# ProPrj_Xros_rev_5_2026-01-20.net
KiCad netlist of a schematic drawn in EasyEDA Pro
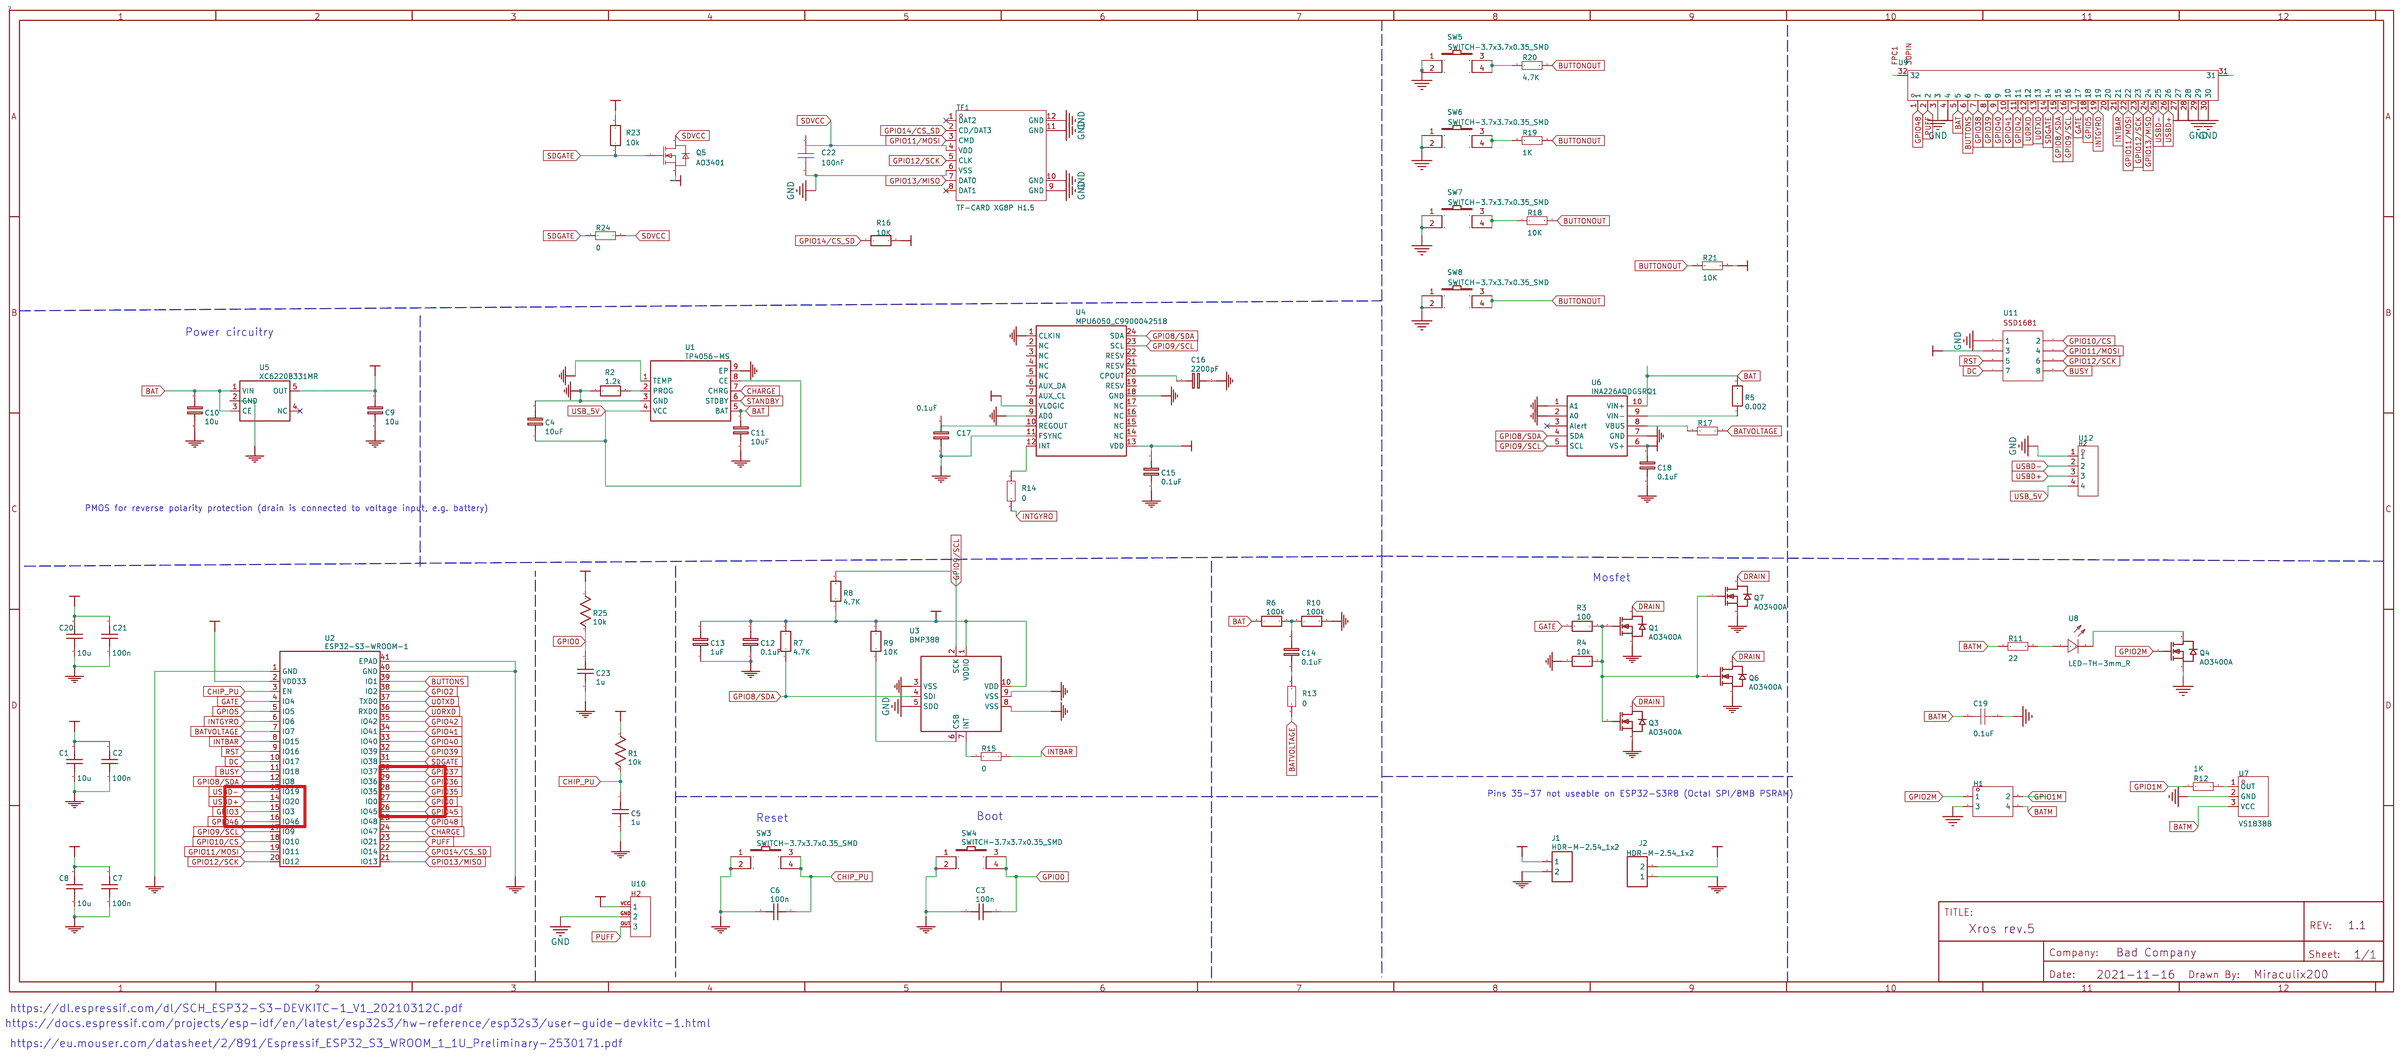
[diagram p0: schematic sheet]

(export (version "E")
  (design (tool "Eeschema 10.0.6"))
  (components
    (comp (ref "C1")
      (value "10u")
      (footprint "easyedapro:C0805")
      (fields (field (name "Contributor") "LCEDA_Lib"))
      (libsource (lib "easyedapro") (part "10u"))
    )
    (comp (ref "C2")
      (value "100n")
      (footprint "easyedapro:C0603")
      (fields (field (name "Contributor") "LCEDA_Lib"))
      (libsource (lib "easyedapro") (part "100n"))
    )
    (comp (ref "C3")
      (value "100n")
      (footprint "easyedapro:C0603")
      (fields (field (name "Contributor") "LCEDA_Lib"))
      (libsource (lib "easyedapro") (part "100n"))
    )
    (comp (ref "C4")
      (value "10uF")
      (footprint "easyedapro:C0603")
      (fields (field (name "Contributor") "LCEDA_Lib"))
      (libsource (lib "") (part "10uF_1"))
    )
    (comp (ref "C5")
      (value "1u")
      (footprint "easyedapro:C0603")
      (fields (field (name "Contributor") "LCEDA_Lib"))
      (libsource (lib "easyedapro") (part "1u"))
    )
    (comp (ref "C6")
      (value "100n")
      (footprint "easyedapro:C0603")
      (fields (field (name "Contributor") "LCEDA_Lib"))
      (libsource (lib "easyedapro") (part "100n"))
    )
    (comp (ref "C7")
      (value "100n")
      (footprint "easyedapro:C0603")
      (fields (field (name "Contributor") "LCEDA_Lib"))
      (libsource (lib "easyedapro") (part "100n"))
    )
    (comp (ref "C8")
      (value "10u")
      (footprint "easyedapro:C0805")
      (fields (field (name "Contributor") "LCEDA_Lib"))
      (libsource (lib "easyedapro") (part "10u"))
    )
    (comp (ref "C9")
      (value "10u")
      (footprint "easyedapro:C0805")
      (fields
        (field (name "Manufacturer Part") "CL10A105KB8NNNC")
        (field (name "Manufacturer") "SAMSUNG")
        (field (name "Contributor") "LCEDA_Lib")
      )
      (libsource (lib "") (part "10u_1"))
    )
    (comp (ref "C10")
      (value "10u")
      (footprint "easyedapro:C0805")
      (fields
        (field (name "Manufacturer Part") "CL10A105KB8NNNC")
        (field (name "Manufacturer") "SAMSUNG")
        (field (name "Contributor") "LCEDA_Lib")
      )
      (libsource (lib "") (part "10u_1"))
    )
    (comp (ref "C11")
      (value "10uF")
      (footprint "easyedapro:C0603")
      (fields (field (name "Contributor") "LCEDA_Lib"))
      (libsource (lib "easyedapro") (part "10uF"))
    )
    (comp (ref "C12")
      (value "0.1uF")
      (footprint "easyedapro:C0603")
      (fields (field (name "Contributor") "LCEDA_Lib"))
      (libsource (lib "") (part "0.1uF_2"))
    )
    (comp (ref "C13")
      (value "1uF")
      (footprint "easyedapro:C0603")
      (fields (field (name "Contributor") "LCEDA_Lib"))
      (libsource (lib "easyedapro") (part "1uF"))
    )
    (comp (ref "C14")
      (value "0.1uF")
      (footprint "easyedapro:C0603")
      (fields (field (name "Contributor") "LCEDA_Lib"))
      (libsource (lib "") (part "0.1uF_2"))
    )
    (comp (ref "C15")
      (value "0.1uF")
      (footprint "easyedapro:C0603")
      (fields (field (name "Contributor") "LCEDA_Lib"))
      (libsource (lib "") (part "0.1uF_2"))
    )
    (comp (ref "C16")
      (value "2200pF")
      (footprint "easyedapro:C0603")
      (fields (field (name "Contributor") "LCEDA_Lib"))
      (libsource (lib "easyedapro") (part "2200pF"))
    )
    (comp (ref "C17")
      (value "0.1uF")
      (footprint "easyedapro:C0603")
      (fields (field (name "Contributor") "LCEDA_Lib"))
      (libsource (lib "easyedapro") (part "0.1uF"))
    )
    (comp (ref "C18")
      (value "0.1uF")
      (footprint "easyedapro:C0603")
      (fields (field (name "Contributor") "LCEDA_Lib"))
      (libsource (lib "") (part "0.1uF_1"))
    )
    (comp (ref "C19")
      (value "0.1uF")
      (footprint "easyedapro:C0201")
      (libsource (lib "easyedapro") (part "CAP"))
    )
    (comp (ref "C20")
      (value "10u")
      (footprint "easyedapro:C0805")
      (fields (field (name "Contributor") "LCEDA_Lib"))
      (libsource (lib "easyedapro") (part "10u"))
    )
    (comp (ref "C21")
      (value "100n")
      (footprint "easyedapro:C0603")
      (fields (field (name "Contributor") "LCEDA_Lib"))
      (libsource (lib "easyedapro") (part "100n"))
    )
    (comp (ref "C22")
      (value "100nF")
      (footprint "easyedapro:C0201")
      (libsource (lib "easyedapro") (part "CAP"))
    )
    (comp (ref "C23")
      (value "1u")
      (footprint "easyedapro:C0603")
      (fields (field (name "Contributor") "LCEDA_Lib"))
      (libsource (lib "easyedapro") (part "1u"))
    )
    (comp (ref "H1")
      (value "~")
      (footprint "easyedapro:HDR-TH_4P-P2.54-V-F-R2-C2-S2.54")
      (libsource (lib "easyedapro") (part "HDR-F-2.54_2x2"))
    )
    (comp (ref "J1")
      (value "HDR-M-2.54_1x2")
      (footprint "easyedapro:HDR-M-2.54_1X2")
      (fields (field (name "Contributor") "LCEDA_Lib"))
      (libsource (lib "easyedapro") (part "HDR-M-2.54_1x2"))
    )
    (comp (ref "J2")
      (value "HDR-M-2.54_1x2")
      (footprint "easyedapro:HDR-M-2.54_1X2")
      (fields (field (name "Contributor") "LCEDA_Lib"))
      (libsource (lib "") (part "HDR-M-2.54_1x2_1"))
    )
    (comp (ref "Q1")
      (value "AO3400A")
      (footprint "easyedapro:SOT-23-3_L2.9-W1.3-P1.90-LS2.4-BR")
      (fields (field (name "Manufacturer") "AOS"))
      (libsource (lib "easyedapro") (part "AO3400A"))
    )
    (comp (ref "Q3")
      (value "AO3400A")
      (footprint "easyedapro:SOT-23-3_L2.9-W1.3-P1.90-LS2.4-BR")
      (fields (field (name "Manufacturer") "AOS"))
      (libsource (lib "easyedapro") (part "AO3400A"))
    )
    (comp (ref "Q4")
      (value "AO3400A")
      (footprint "easyedapro:SOT-23-3_L2.9-W1.3-P1.90-LS2.4-BR")
      (fields (field (name "Manufacturer") "AOS"))
      (libsource (lib "easyedapro") (part "AO3400A"))
    )
    (comp (ref "Q5")
      (value "AO3401")
      (footprint "easyedapro:SOT-23-3_L2.9-W1.4-P1.90-LS2.5-BR")
      (fields (field (name "Manufacturer") "GMIC(绿微)"))
      (libsource (lib "easyedapro") (part "AO3401_C53261043"))
    )
    (comp (ref "Q6")
      (value "AO3400A")
      (footprint "easyedapro:SOT-23-3_L2.9-W1.3-P1.90-LS2.4-BR")
      (fields (field (name "Manufacturer") "AOS"))
      (libsource (lib "easyedapro") (part "AO3400A"))
    )
    (comp (ref "Q7")
      (value "AO3400A")
      (footprint "easyedapro:SOT-23-3_L2.9-W1.3-P1.90-LS2.4-BR")
      (fields (field (name "Manufacturer") "AOS"))
      (libsource (lib "easyedapro") (part "AO3400A"))
    )
    (comp (ref "R1")
      (value "10k")
      (footprint "easyedapro:R0603")
      (fields (field (name "Contributor") "LCEDA_Lib"))
      (libsource (lib "") (part "10k_2"))
    )
    (comp (ref "R2")
      (value "1.2k")
      (footprint "easyedapro:R0603")
      (fields (field (name "Contributor") "LCEDA_Lib"))
      (libsource (lib "easyedapro") (part "1.2k"))
    )
    (comp (ref "R3")
      (value "100")
      (footprint "easyedapro:R0603")
      (fields (field (name "Contributor") "LCEDA_Lib"))
      (libsource (lib "easyedapro") (part "100"))
    )
    (comp (ref "R4")
      (value "10k")
      (footprint "easyedapro:R0603")
      (fields (field (name "Contributor") "LCEDA_Lib"))
      (libsource (lib "easyedapro") (part "10k"))
    )
    (comp (ref "R5")
      (value "0.002")
      (footprint "easyedapro:R0603")
      (fields (field (name "Contributor") "LCEDA_Lib"))
      (libsource (lib "easyedapro") (part "0.002"))
    )
    (comp (ref "R6")
      (value "100k")
      (footprint "easyedapro:R0603")
      (fields (field (name "Contributor") "LCEDA_Lib"))
      (libsource (lib "easyedapro") (part "100k"))
    )
    (comp (ref "R7")
      (value "4.7K")
      (footprint "easyedapro:R0603")
      (fields (field (name "Contributor") "LCEDA_Lib"))
      (libsource (lib "") (part "10k_1"))
    )
    (comp (ref "R8")
      (value "4.7K")
      (footprint "easyedapro:R0603")
      (fields (field (name "Contributor") "LCEDA_Lib"))
      (libsource (lib "easyedapro") (part "10K"))
    )
    (comp (ref "R9")
      (value "10K")
      (footprint "easyedapro:R0603")
      (fields (field (name "Contributor") "LCEDA_Lib"))
      (libsource (lib "easyedapro") (part "10K"))
    )
    (comp (ref "R10")
      (value "100k")
      (footprint "easyedapro:R0603")
      (fields (field (name "Contributor") "LCEDA_Lib"))
      (libsource (lib "easyedapro") (part "100k"))
    )
    (comp (ref "R11") (value "22") (footprint "easyedapro:R0805") (libsource (lib "easyedapro") (part "Res")))
    (comp (ref "R12") (value "1K") (footprint "easyedapro:R0805") (libsource (lib "easyedapro") (part "Res")))
    (comp (ref "R13") (value "0") (footprint "easyedapro:R0805") (libsource (lib "easyedapro") (part "Res")))
    (comp (ref "R14") (value "0") (footprint "easyedapro:R0805") (libsource (lib "easyedapro") (part "Res")))
    (comp (ref "R15") (value "0") (footprint "easyedapro:R0805") (libsource (lib "easyedapro") (part "Res")))
    (comp (ref "R16")
      (value "10K")
      (footprint "easyedapro:R0603")
      (fields (field (name "Contributor") "LCEDA_Lib"))
      (libsource (lib "easyedapro") (part "1.2k"))
    )
    (comp (ref "R17") (value "0") (footprint "easyedapro:R0805") (libsource (lib "easyedapro") (part "Res")))
    (comp (ref "R18")
      (value "10K")
      (footprint "easyedapro:R0805")
      (libsource (lib "easyedapro") (part "Res"))
    )
    (comp (ref "R19") (value "1K") (footprint "easyedapro:R0805") (libsource (lib "easyedapro") (part "Res")))
    (comp (ref "R20")
      (value "4.7K")
      (footprint "easyedapro:R0805")
      (libsource (lib "easyedapro") (part "Res"))
    )
    (comp (ref "R21")
      (value "10K")
      (footprint "easyedapro:R0805")
      (libsource (lib "easyedapro") (part "Res"))
    )
    (comp (ref "R23")
      (value "10k")
      (footprint "easyedapro:R0603")
      (fields (field (name "Contributor") "LCEDA_Lib"))
      (libsource (lib "easyedapro") (part "10k"))
    )
    (comp (ref "R24") (value "0") (footprint "easyedapro:R0805") (libsource (lib "easyedapro") (part "Res")))
    (comp (ref "R25")
      (value "10k")
      (footprint "easyedapro:R0603")
      (fields (field (name "Contributor") "LCEDA_Lib"))
      (libsource (lib "") (part "10k_2"))
    )
    (comp (ref "SW3")
      (value "SWITCH-3.7x3.7x0.35_SMD")
      (footprint "easyedapro:SWITCH-3.7X3.7X0.8_SMD")
      (fields (field (name "Manufacturer") "BBJ") (field (name "Contributor") "Conrad Lagorio"))
      (libsource (lib "easyedapro") (part "SWITCH-3.7x3.7x0.35_SMD"))
    )
    (comp (ref "SW4")
      (value "SWITCH-3.7x3.7x0.35_SMD")
      (footprint "easyedapro:SWITCH-3.7X3.7X0.8_SMD")
      (fields (field (name "Manufacturer") "BBJ") (field (name "Contributor") "Conrad Lagorio"))
      (libsource (lib "easyedapro") (part "SWITCH-3.7x3.7x0.35_SMD"))
    )
    (comp (ref "SW5")
      (value "SWITCH-3.7x3.7x0.35_SMD")
      (footprint "easyedapro:SWITCH-3.7X3.7X0.8_SMD")
      (fields (field (name "Manufacturer") "BBJ") (field (name "Contributor") "Conrad Lagorio"))
      (libsource (lib "easyedapro") (part "SWITCH-3.7x3.7x0.35_SMD"))
    )
    (comp (ref "SW6")
      (value "SWITCH-3.7x3.7x0.35_SMD")
      (footprint "easyedapro:SWITCH-3.7X3.7X0.8_SMD")
      (fields (field (name "Manufacturer") "BBJ") (field (name "Contributor") "Conrad Lagorio"))
      (libsource (lib "easyedapro") (part "SWITCH-3.7x3.7x0.35_SMD"))
    )
    (comp (ref "SW7")
      (value "SWITCH-3.7x3.7x0.35_SMD")
      (footprint "easyedapro:SWITCH-3.7X3.7X0.8_SMD")
      (fields (field (name "Manufacturer") "BBJ") (field (name "Contributor") "Conrad Lagorio"))
      (libsource (lib "easyedapro") (part "SWITCH-3.7x3.7x0.35_SMD"))
    )
    (comp (ref "SW8")
      (value "SWITCH-3.7x3.7x0.35_SMD")
      (footprint "easyedapro:SWITCH-3.7X3.7X0.8_SMD")
      (fields (field (name "Manufacturer") "BBJ") (field (name "Contributor") "Conrad Lagorio"))
      (libsource (lib "easyedapro") (part "SWITCH-3.7x3.7x0.35_SMD"))
    )
    (comp (ref "TF1")
      (value "TF-CARD XG8P H1.5")
      (footprint "easyedapro:TF-SMD_TF-CARD-XG8P-H1.5")
      (fields (field (name "Manufacturer") "SHOU HAN(首韩)"))
      (libsource (lib "easyedapro") (part "TF-CARD XG8P H1.5"))
    )
    (comp (ref "U1")
      (value "TP4056-MS")
      (footprint "easyedapro:SOP-8_L4.9-W3.9-P1.27-LS6.0-TL-EP")
      (fields (field (name "Manufacturer") "MSKSEMI(美森科)") (field (name "Contributor") "lcsc"))
      (libsource (lib "easyedapro") (part "TP4056-MS"))
    )
    (comp (ref "U2")
      (value "ESP32-S3-WROOM-1")
      (footprint "easyedapro:ESP32-S3-WROOM-1")
      (fields (field (name "Manufacturer") "Espressif Systems") (field (name "Contributor") "max30012540"))
      (libsource (lib "easyedapro") (part "ESP32-S3-WROOM-1"))
    )
    (comp (ref "U3")
      (value "BMP388")
      (footprint "easyedapro:SENSORM-SMD_BMP388")
      (fields (field (name "Manufacturer") "Bosch(博世)") (field (name "Contributor") "LCSC"))
      (libsource (lib "easyedapro") (part "BMP388"))
    )
    (comp (ref "U4")
      (value "MPU6050_C9900042518")
      (footprint "easyedapro:QFN-24_L4.0-W4.0-P0.50-BL")
      (fields (field (name "Manufacturer Part") "MPU6050") (field (name "Contributor") "lcsc"))
      (libsource (lib "easyedapro") (part "MPU6050_C9900042518"))
    )
    (comp (ref "U5")
      (value "XC6220B331MR")
      (footprint "easyedapro:SOT-23-5_L2.9-W1.6-P0.95-LS2.8-BR")
      (fields (field (name "Manufacturer") "TECH PUBLIC(台舟)") (field (name "Contributor") "lcsc"))
      (libsource (lib "easyedapro") (part "XC6220B331MR"))
    )
    (comp (ref "U6")
      (value "INA226AQDGSRQ1")
      (footprint "easyedapro:VSSOP-10_L3.0-W3.0-P0.50-LS4.9-BL")
      (fields (field (name "Manufacturer") "TI(德州仪器)") (field (name "Contributor") "lcsc"))
      (libsource (lib "easyedapro") (part "INA226AQDGSRQ1"))
    )
    (comp (ref "U7")
      (value "VS1838B")
      (footprint "easyedapro:OPTO-TH_VS1838B")
      (libsource (lib "easyedapro") (part "VS1838B"))
    )
    (comp (ref "U8")
      (value "LED-TH-3mm_R")
      (footprint "easyedapro:LED-TH_BD5.4-P2.54-FD_RED")
      (libsource (lib "easyedapro") (part "LED-TH-3MM_R"))
    )
    (comp (ref "U9")
      (value "~")
      (footprint "easyedapro:26PIN-FDD")
      (libsource (lib "easyedapro") (part "26PIN-dff"))
    )
    (comp (ref "U10")
      (value "~")
      (footprint "easyedapro:Puff sensor")
      (libsource (lib "easyedapro") (part "Puff sensor"))
    )
    (comp (ref "U11")
      (value "~")
      (footprint "easyedapro:HDR-TH_8P-P0.6")
      (libsource (lib "easyedapro") (part "HDR-TH_8P-P0.6"))
    )
    (comp (ref "U12")
      (value "~")
      (footprint "easyedapro:USB-CONNECTOR-4-PIN")
      (libsource (lib "easyedapro") (part "USB-CONNECTOR-OUT"))
    )
  )
  (nets
    (net (code "1") (name "3V3") (class "Default")
      (node (ref "C1") (pin "2") (pinfunction "2_2") (pintype "unspecified"))
      (node (ref "C12") (pin "2") (pinfunction "2_2") (pintype "unspecified"))
      (node (ref "C13") (pin "2") (pinfunction "2_2") (pintype "unspecified"))
      (node (ref "C15") (pin "2") (pinfunction "2_2") (pintype "unspecified"))
      (node (ref "C18") (pin "1") (pinfunction "1_1") (pintype "unspecified"))
      (node (ref "C2") (pin "2") (pinfunction "2_2") (pintype "unspecified"))
      (node (ref "C20") (pin "2") (pinfunction "2_2") (pintype "unspecified"))
      (node (ref "C21") (pin "2") (pinfunction "2_2") (pintype "unspecified"))
      (node (ref "C7") (pin "2") (pinfunction "2_2") (pintype "unspecified"))
      (node (ref "C8") (pin "2") (pinfunction "2_2") (pintype "unspecified"))
      (node (ref "C9") (pin "1") (pinfunction "1_1") (pintype "unspecified"))
      (node (ref "J1") (pin "1") (pinfunction "1_1") (pintype "unspecified"))
      (node (ref "Q5") (pin "2") (pinfunction "S_2") (pintype "unspecified"))
      (node (ref "R1") (pin "1") (pinfunction "1_1") (pintype "unspecified"))
      (node (ref "R16") (pin "2") (pinfunction "2_2") (pintype "unspecified"))
      (node (ref "R23") (pin "2") (pinfunction "2_2") (pintype "unspecified"))
      (node (ref "R25") (pin "1") (pinfunction "1_1") (pintype "unspecified"))
      (node (ref "R7") (pin "2") (pinfunction "2_2") (pintype "unspecified"))
      (node (ref "R8") (pin "1") (pinfunction "1_1") (pintype "unspecified"))
      (node (ref "R9") (pin "2") (pinfunction "2_2") (pintype "unspecified"))
      (node (ref "U10") (pin "VCC") (pinfunction "1_VCC") (pintype "unspecified"))
      (node (ref "U11") (pin "3") (pinfunction "3_3") (pintype "input"))
      (node (ref "U2") (pin "2") (pinfunction "VDD33_2") (pintype "unspecified"))
      (node (ref "U3") (pin "1") (pinfunction "VDDIO_1") (pintype "unspecified"))
      (node (ref "U3") (pin "10") (pinfunction "VDD_10") (pintype "unspecified"))
      (node (ref "U4") (pin "13") (pinfunction "VDD_13") (pintype "unspecified"))
      (node (ref "U4") (pin "8") (pinfunction "VLOGIC_8") (pintype "unspecified"))
      (node (ref "U5") (pin "5") (pinfunction "OUT_5") (pintype "unspecified"))
      (node (ref "U6") (pin "6") (pinfunction "VS+_6") (pintype "unspecified"))
      (node (ref "U9") (pin "27") (pinfunction "27_27") (pintype "input"))
      (node (ref "U9") (pin "28") (pinfunction "28_28") (pintype "input"))
      (node (ref "U9") (pin "4") (pinfunction "4_4") (pintype "input"))
    )
    (net (code "2") (name "3V3_BUT") (class "Default")
      (node (ref "R21") (pin "2") (pinfunction "2_2") (pintype "input"))
    )
    (net (code "3") (name "BAT") (class "Default")
      (node (ref "C10") (pin "1") (pinfunction "1_1") (pintype "unspecified"))
      (node (ref "C11") (pin "1") (pinfunction "1_1") (pintype "unspecified"))
      (node (ref "R5") (pin "2") (pinfunction "2_2") (pintype "unspecified"))
      (node (ref "R6") (pin "1") (pinfunction "1_1") (pintype "unspecified"))
      (node (ref "U1") (pin "5") (pinfunction "BAT_5") (pintype "unspecified"))
      (node (ref "U5") (pin "1") (pinfunction "VIN_1") (pintype "unspecified"))
      (node (ref "U5") (pin "3") (pinfunction "CE_3") (pintype "unspecified"))
      (node (ref "U6") (pin "10") (pinfunction "VIN+_10") (pintype "unspecified"))
      (node (ref "U9") (pin "5") (pinfunction "5_5") (pintype "input"))
    )
    (net (code "4") (name "BATM") (class "Default")
      (node (ref "C19") (pin "2") (pinfunction "2_2") (pintype "input"))
      (node (ref "H1") (pin "4") (pinfunction "4_4") (pintype "input"))
      (node (ref "R11") (pin "1") (pinfunction "1_1") (pintype "input"))
      (node (ref "U7") (pin "3") (pinfunction "VCC_3") (pintype "unspecified"))
    )
    (net (code "5") (name "BATVOLTAGE") (class "Default")
      (node (ref "R13") (pin "1") (pinfunction "1_1") (pintype "input"))
      (node (ref "R17") (pin "2") (pinfunction "2_2") (pintype "input"))
      (node (ref "U2") (pin "7") (pinfunction "IO7_7") (pintype "unspecified"))
    )
    (net (code "6") (name "BUSY") (class "Default")
      (node (ref "U11") (pin "8") (pinfunction "8_8") (pintype "input"))
      (node (ref "U2") (pin "11") (pinfunction "IO18_11") (pintype "unspecified"))
    )
    (net (code "7") (name "BUTTONOUT") (class "Default")
      (node (ref "R18") (pin "2") (pinfunction "2_2") (pintype "input"))
      (node (ref "R19") (pin "2") (pinfunction "2_2") (pintype "input"))
      (node (ref "R20") (pin "2") (pinfunction "2_2") (pintype "input"))
      (node (ref "R21") (pin "1") (pinfunction "1_1") (pintype "input"))
      (node (ref "SW8") (pin "3") (pinfunction "3_3") (pintype "input"))
      (node (ref "SW8") (pin "4") (pinfunction "4_4") (pintype "input"))
    )
    (net (code "8") (name "BUTTONS") (class "Default")
      (node (ref "U2") (pin "39") (pinfunction "IO1_39") (pintype "unspecified"))
      (node (ref "U9") (pin "6") (pinfunction "6_6") (pintype "input"))
    )
    (net (code "9") (name "CHARGE") (class "Default")
      (node (ref "U1") (pin "7") (pinfunction "CHRG_7") (pintype "unspecified"))
      (node (ref "U2") (pin "24") (pinfunction "IO47_24") (pintype "unspecified"))
    )
    (net (code "10") (name "CHIP_PU") (class "Default")
      (node (ref "C5") (pin "1") (pinfunction "1_1") (pintype "unspecified"))
      (node (ref "C6") (pin "1") (pinfunction "1_1") (pintype "unspecified"))
      (node (ref "R1") (pin "2") (pinfunction "2_2") (pintype "unspecified"))
      (node (ref "SW3") (pin "3") (pinfunction "3_3") (pintype "input"))
      (node (ref "SW3") (pin "4") (pinfunction "4_4") (pintype "input"))
      (node (ref "U2") (pin "3") (pinfunction "EN_3") (pintype "unspecified"))
    )
    (net (code "11") (name "DC") (class "Default")
      (node (ref "U11") (pin "7") (pinfunction "7_7") (pintype "input"))
      (node (ref "U2") (pin "10") (pinfunction "IO17_10") (pintype "unspecified"))
    )
    (net (code "12") (name "DRAIN") (class "Default")
      (node (ref "Q1") (pin "3") (pinfunction "D_3") (pintype "unspecified"))
      (node (ref "Q3") (pin "3") (pinfunction "D_3") (pintype "unspecified"))
      (node (ref "Q6") (pin "3") (pinfunction "D_3") (pintype "unspecified"))
      (node (ref "Q7") (pin "3") (pinfunction "D_3") (pintype "unspecified"))
    )
    (net (code "13") (name "GATE") (class "Default")
      (node (ref "R3") (pin "1") (pinfunction "1_1") (pintype "unspecified"))
      (node (ref "U2") (pin "4") (pinfunction "IO4_4") (pintype "unspecified"))
      (node (ref "U9") (pin "17") (pinfunction "17_17") (pintype "input"))
    )
    (net (code "14") (name "GND") (class "Default")
      (node (ref "C1") (pin "1") (pinfunction "1_1") (pintype "unspecified"))
      (node (ref "C10") (pin "2") (pinfunction "2_2") (pintype "unspecified"))
      (node (ref "C11") (pin "2") (pinfunction "2_2") (pintype "unspecified"))
      (node (ref "C12") (pin "1") (pinfunction "1_1") (pintype "unspecified"))
      (node (ref "C13") (pin "1") (pinfunction "1_1") (pintype "unspecified"))
      (node (ref "C15") (pin "1") (pinfunction "1_1") (pintype "unspecified"))
      (node (ref "C16") (pin "2") (pinfunction "2_2") (pintype "unspecified"))
      (node (ref "C17") (pin "2") (pinfunction "2_2") (pintype "unspecified"))
      (node (ref "C18") (pin "2") (pinfunction "2_2") (pintype "unspecified"))
      (node (ref "C2") (pin "1") (pinfunction "1_1") (pintype "unspecified"))
      (node (ref "C20") (pin "1") (pinfunction "1_1") (pintype "unspecified"))
      (node (ref "C21") (pin "1") (pinfunction "1_1") (pintype "unspecified"))
      (node (ref "C22") (pin "2") (pinfunction "2_2") (pintype "input"))
      (node (ref "C23") (pin "2") (pinfunction "2_2") (pintype "unspecified"))
      (node (ref "C3") (pin "2") (pinfunction "2_2") (pintype "unspecified"))
      (node (ref "C4") (pin "2") (pinfunction "2_2") (pintype "unspecified"))
      (node (ref "C5") (pin "2") (pinfunction "2_2") (pintype "unspecified"))
      (node (ref "C6") (pin "2") (pinfunction "2_2") (pintype "unspecified"))
      (node (ref "C7") (pin "1") (pinfunction "1_1") (pintype "unspecified"))
      (node (ref "C8") (pin "1") (pinfunction "1_1") (pintype "unspecified"))
      (node (ref "C9") (pin "2") (pinfunction "2_2") (pintype "unspecified"))
      (node (ref "J1") (pin "2") (pinfunction "2_2") (pintype "unspecified"))
      (node (ref "J2") (pin "1") (pinfunction "1_1") (pintype "unspecified"))
      (node (ref "Q1") (pin "2") (pinfunction "S_2") (pintype "unspecified"))
      (node (ref "Q3") (pin "2") (pinfunction "S_2") (pintype "unspecified"))
      (node (ref "Q6") (pin "2") (pinfunction "S_2") (pintype "unspecified"))
      (node (ref "Q7") (pin "2") (pinfunction "S_2") (pintype "unspecified"))
      (node (ref "R10") (pin "2") (pinfunction "2_2") (pintype "unspecified"))
      (node (ref "R2") (pin "1") (pinfunction "1_1") (pintype "unspecified"))
      (node (ref "R4") (pin "1") (pinfunction "1_1") (pintype "unspecified"))
      (node (ref "SW3") (pin "1") (pinfunction "1_1") (pintype "input"))
      (node (ref "SW3") (pin "2") (pinfunction "2_2") (pintype "input"))
      (node (ref "SW4") (pin "1") (pinfunction "1_1") (pintype "input"))
      (node (ref "SW4") (pin "2") (pinfunction "2_2") (pintype "input"))
      (node (ref "TF1") (pin "10") (pinfunction "GND_10") (pintype "unspecified"))
      (node (ref "TF1") (pin "11") (pinfunction "GND_11") (pintype "unspecified"))
      (node (ref "TF1") (pin "12") (pinfunction "GND_12") (pintype "unspecified"))
      (node (ref "TF1") (pin "6") (pinfunction "VSS_6") (pintype "unspecified"))
      (node (ref "TF1") (pin "9") (pinfunction "GND_9") (pintype "unspecified"))
      (node (ref "U1") (pin "1") (pinfunction "TEMP_1") (pintype "unspecified"))
      (node (ref "U1") (pin "3") (pinfunction "GND_3") (pintype "unspecified"))
      (node (ref "U1") (pin "9") (pinfunction "EP_9") (pintype "unspecified"))
      (node (ref "U10") (pin "GND") (pinfunction "2_GND") (pintype "unspecified"))
      (node (ref "U11") (pin "1") (pinfunction "1_1") (pintype "input"))
      (node (ref "U12") (pin "1") (pinfunction "1_1") (pintype "input"))
      (node (ref "U2") (pin "1") (pinfunction "GND_1") (pintype "unspecified"))
      (node (ref "U2") (pin "40") (pinfunction "GND_40") (pintype "unspecified"))
      (node (ref "U2") (pin "41") (pinfunction "EPAD_41") (pintype "unspecified"))
      (node (ref "U3") (pin "3") (pinfunction "VSS_3") (pintype "unspecified"))
      (node (ref "U3") (pin "5") (pinfunction "SDO_5") (pintype "unspecified"))
      (node (ref "U3") (pin "8") (pinfunction "VSS_8") (pintype "unspecified"))
      (node (ref "U3") (pin "9") (pinfunction "VSS_9") (pintype "unspecified"))
      (node (ref "U4") (pin "1") (pinfunction "CLKIN_1") (pintype "unspecified"))
      (node (ref "U4") (pin "11") (pinfunction "FSYNC_11") (pintype "unspecified"))
      (node (ref "U4") (pin "18") (pinfunction "GND_18") (pintype "unspecified"))
      (node (ref "U4") (pin "9") (pinfunction "AD0_9") (pintype "unspecified"))
      (node (ref "U5") (pin "2") (pinfunction "GND_2") (pintype "unspecified"))
      (node (ref "U6") (pin "1") (pinfunction "A1_1") (pintype "unspecified"))
      (node (ref "U6") (pin "2") (pinfunction "A0_2") (pintype "unspecified"))
      (node (ref "U6") (pin "7") (pinfunction "GND_7") (pintype "unspecified"))
      (node (ref "U9") (pin "29") (pinfunction "29_29") (pintype "input"))
      (node (ref "U9") (pin "3") (pinfunction "3_3") (pintype "input"))
      (node (ref "U9") (pin "30") (pinfunction "30_30") (pintype "input"))
    )
    (net (code "15") (name "GNDM") (class "Default")
      (node (ref "C19") (pin "1") (pinfunction "1_1") (pintype "input"))
      (node (ref "H1") (pin "3") (pinfunction "3_3") (pintype "input"))
      (node (ref "Q4") (pin "2") (pinfunction "S_2") (pintype "unspecified"))
      (node (ref "U7") (pin "2") (pinfunction "GND_2") (pintype "unspecified"))
    )
    (net (code "16") (name "GND_BUT") (class "Default")
      (node (ref "SW5") (pin "1") (pinfunction "1_1") (pintype "input"))
      (node (ref "SW5") (pin "2") (pinfunction "2_2") (pintype "input"))
      (node (ref "SW6") (pin "1") (pinfunction "1_1") (pintype "input"))
      (node (ref "SW6") (pin "2") (pinfunction "2_2") (pintype "input"))
      (node (ref "SW7") (pin "1") (pinfunction "1_1") (pintype "input"))
      (node (ref "SW7") (pin "2") (pinfunction "2_2") (pintype "input"))
      (node (ref "SW8") (pin "1") (pinfunction "1_1") (pintype "input"))
      (node (ref "SW8") (pin "2") (pinfunction "2_2") (pintype "input"))
    )
    (net (code "17") (name "GPIO0") (class "Default")
      (node (ref "C23") (pin "1") (pinfunction "1_1") (pintype "unspecified"))
      (node (ref "C3") (pin "1") (pinfunction "1_1") (pintype "unspecified"))
      (node (ref "R25") (pin "2") (pinfunction "2_2") (pintype "unspecified"))
      (node (ref "SW4") (pin "3") (pinfunction "3_3") (pintype "input"))
      (node (ref "SW4") (pin "4") (pinfunction "4_4") (pintype "input"))
      (node (ref "U2") (pin "27") (pinfunction "IO0_27") (pintype "unspecified"))
    )
    (net (code "18") (name "GPIO1M") (class "Default")
      (node (ref "H1") (pin "2") (pinfunction "2_2") (pintype "input"))
      (node (ref "R12") (pin "1") (pinfunction "1_1") (pintype "input"))
    )
    (net (code "19") (name "GPIO2") (class "Default")
      (node (ref "U2") (pin "38") (pinfunction "IO2_38") (pintype "unspecified"))
    )
    (net (code "20") (name "GPIO2M") (class "Default")
      (node (ref "H1") (pin "1") (pinfunction "1_1") (pintype "input"))
      (node (ref "Q4") (pin "1") (pinfunction "G_1") (pintype "unspecified"))
    )
    (net (code "21") (name "GPIO3") (class "Default")
      (node (ref "U2") (pin "15") (pinfunction "IO3_15") (pintype "unspecified"))
    )
    (net (code "22") (name "GPIO5") (class "Default")
      (node (ref "U2") (pin "5") (pinfunction "IO5_5") (pintype "unspecified"))
      (node (ref "U9") (pin "18") (pinfunction "18_18") (pintype "input"))
    )
    (net (code "23") (name "GPIO8{slash}SDA") (class "Default")
      (node (ref "R7") (pin "1") (pinfunction "1_1") (pintype "unspecified"))
      (node (ref "U2") (pin "12") (pinfunction "IO8_12") (pintype "unspecified"))
      (node (ref "U3") (pin "4") (pinfunction "SDI_4") (pintype "unspecified"))
      (node (ref "U4") (pin "24") (pinfunction "SDA_24") (pintype "unspecified"))
      (node (ref "U6") (pin "4") (pinfunction "SDA_4") (pintype "unspecified"))
      (node (ref "U9") (pin "15") (pinfunction "15_15") (pintype "input"))
    )
    (net (code "24") (name "GPIO9{slash}SCL") (class "Default")
      (node (ref "R8") (pin "2") (pinfunction "2_2") (pintype "unspecified"))
      (node (ref "U2") (pin "17") (pinfunction "IO9_17") (pintype "unspecified"))
      (node (ref "U3") (pin "2") (pinfunction "SCK_2") (pintype "unspecified"))
      (node (ref "U4") (pin "23") (pinfunction "SCL_23") (pintype "unspecified"))
      (node (ref "U6") (pin "5") (pinfunction "SCL_5") (pintype "unspecified"))
      (node (ref "U9") (pin "16") (pinfunction "16_16") (pintype "input"))
    )
    (net (code "25") (name "GPIO10{slash}CS") (class "Default")
      (node (ref "U11") (pin "2") (pinfunction "2_2") (pintype "input"))
      (node (ref "U2") (pin "18") (pinfunction "IO10_18") (pintype "unspecified"))
    )
    (net (code "26") (name "GPIO11{slash}MOSI") (class "Default")
      (node (ref "TF1") (pin "3") (pinfunction "CMD_3") (pintype "unspecified"))
      (node (ref "U11") (pin "4") (pinfunction "4_4") (pintype "input"))
      (node (ref "U2") (pin "19") (pinfunction "IO11_19") (pintype "unspecified"))
      (node (ref "U9") (pin "22") (pinfunction "22_22") (pintype "input"))
    )
    (net (code "27") (name "GPIO12{slash}SCK") (class "Default")
      (node (ref "TF1") (pin "5") (pinfunction "CLK_5") (pintype "unspecified"))
      (node (ref "U11") (pin "6") (pinfunction "6_6") (pintype "input"))
      (node (ref "U2") (pin "20") (pinfunction "IO12_20") (pintype "unspecified"))
      (node (ref "U9") (pin "23") (pinfunction "23_23") (pintype "input"))
    )
    (net (code "28") (name "GPIO13{slash}MISO") (class "Default")
      (node (ref "TF1") (pin "7") (pinfunction "DAT0_7") (pintype "unspecified"))
      (node (ref "U2") (pin "21") (pinfunction "IO13_21") (pintype "unspecified"))
      (node (ref "U9") (pin "24") (pinfunction "24_24") (pintype "input"))
    )
    (net (code "29") (name "GPIO14{slash}CS_SD") (class "Default")
      (node (ref "R16") (pin "1") (pinfunction "1_1") (pintype "unspecified"))
      (node (ref "TF1") (pin "2") (pinfunction "CD/DAT3_2") (pintype "unspecified"))
      (node (ref "U2") (pin "22") (pinfunction "IO14_22") (pintype "unspecified"))
    )
    (net (code "30") (name "GPIO35") (class "Default")
      (node (ref "U2") (pin "28") (pinfunction "IO35_28") (pintype "unspecified"))
    )
    (net (code "31") (name "GPIO36") (class "Default")
      (node (ref "U2") (pin "29") (pinfunction "IO36_29") (pintype "unspecified"))
    )
    (net (code "32") (name "GPIO37") (class "Default")
      (node (ref "U2") (pin "30") (pinfunction "IO37_30") (pintype "unspecified"))
    )
    (net (code "33") (name "GPIO38") (class "Default")
      (node (ref "U9") (pin "7") (pinfunction "7_7") (pintype "input"))
    )
    (net (code "34") (name "GPIO39") (class "Default")
      (node (ref "U2") (pin "32") (pinfunction "IO39_32") (pintype "unspecified"))
      (node (ref "U9") (pin "8") (pinfunction "8_8") (pintype "input"))
    )
    (net (code "35") (name "GPIO40") (class "Default")
      (node (ref "U2") (pin "33") (pinfunction "IO40_33") (pintype "unspecified"))
      (node (ref "U9") (pin "9") (pinfunction "9_9") (pintype "input"))
    )
    (net (code "36") (name "GPIO41") (class "Default")
      (node (ref "U2") (pin "34") (pinfunction "IO41_34") (pintype "unspecified"))
      (node (ref "U9") (pin "10") (pinfunction "10_10") (pintype "input"))
    )
    (net (code "37") (name "GPIO42") (class "Default")
      (node (ref "U2") (pin "35") (pinfunction "IO42_35") (pintype "unspecified"))
      (node (ref "U9") (pin "11") (pinfunction "11_11") (pintype "input"))
    )
    (net (code "38") (name "GPIO45") (class "Default")
      (node (ref "U2") (pin "26") (pinfunction "IO45_26") (pintype "unspecified"))
    )
    (net (code "39") (name "GPIO46") (class "Default")
      (node (ref "U2") (pin "16") (pinfunction "IO46_16") (pintype "unspecified"))
    )
    (net (code "40") (name "GPIO48") (class "Default")
      (node (ref "U2") (pin "25") (pinfunction "IO48_25") (pintype "unspecified"))
      (node (ref "U9") (pin "1") (pinfunction "1_1") (pintype "input"))
    )
    (net (code "41") (name "INTBAR") (class "Default")
      (node (ref "R15") (pin "2") (pinfunction "2_2") (pintype "input"))
      (node (ref "U2") (pin "8") (pinfunction "IO15_8") (pintype "unspecified"))
      (node (ref "U9") (pin "21") (pinfunction "21_21") (pintype "input"))
    )
    (net (code "42") (name "INTGYRO") (class "Default")
      (node (ref "R14") (pin "2") (pinfunction "2_2") (pintype "input"))
      (node (ref "U2") (pin "6") (pinfunction "IO6_6") (pintype "unspecified"))
      (node (ref "U9") (pin "19") (pinfunction "19_19") (pintype "input"))
    )
    (net (code "43") (name "Net-(C14-Pad1)") (class "Default")
      (node (ref "C14") (pin "1") (pinfunction "1_1") (pintype "unspecified"))
      (node (ref "R13") (pin "2") (pinfunction "2_2") (pintype "input"))
    )
    (net (code "44") (name "Net-(C14-Pad2)") (class "Default")
      (node (ref "C14") (pin "2") (pinfunction "2_2") (pintype "unspecified"))
      (node (ref "R10") (pin "1") (pinfunction "1_1") (pintype "unspecified"))
      (node (ref "R6") (pin "2") (pinfunction "2_2") (pintype "unspecified"))
    )
    (net (code "45") (name "Net-(Q1-G)") (class "Default")
      (node (ref "Q1") (pin "1") (pinfunction "G_1") (pintype "unspecified"))
      (node (ref "Q3") (pin "1") (pinfunction "G_1") (pintype "unspecified"))
      (node (ref "Q6") (pin "1") (pinfunction "G_1") (pintype "unspecified"))
      (node (ref "Q7") (pin "1") (pinfunction "G_1") (pintype "unspecified"))
      (node (ref "R3") (pin "2") (pinfunction "2_2") (pintype "unspecified"))
      (node (ref "R4") (pin "2") (pinfunction "2_2") (pintype "unspecified"))
    )
    (net (code "46") (name "Net-(Q4-D)") (class "Default")
      (node (ref "Q4") (pin "3") (pinfunction "D_3") (pintype "unspecified"))
      (node (ref "U8") (pin "2") (pinfunction "2_2") (pintype "unspecified"))
    )
    (net (code "47") (name "Net-(R11-Pad2)") (class "Default")
      (node (ref "R11") (pin "2") (pinfunction "2_2") (pintype "input"))
      (node (ref "U8") (pin "1") (pinfunction "1_1") (pintype "unspecified"))
    )
    (net (code "48") (name "Net-(R18-Pad1)") (class "Default")
      (node (ref "R18") (pin "1") (pinfunction "1_1") (pintype "input"))
      (node (ref "SW7") (pin "3") (pinfunction "3_3") (pintype "input"))
      (node (ref "SW7") (pin "4") (pinfunction "4_4") (pintype "input"))
    )
    (net (code "49") (name "Net-(R19-Pad1)") (class "Default")
      (node (ref "R19") (pin "1") (pinfunction "1_1") (pintype "input"))
      (node (ref "SW6") (pin "3") (pinfunction "3_3") (pintype "input"))
      (node (ref "SW6") (pin "4") (pinfunction "4_4") (pintype "input"))
    )
    (net (code "50") (name "Net-(R20-Pad1)") (class "Default")
      (node (ref "R20") (pin "1") (pinfunction "1_1") (pintype "input"))
      (node (ref "SW5") (pin "3") (pinfunction "3_3") (pintype "input"))
      (node (ref "SW5") (pin "4") (pinfunction "4_4") (pintype "input"))
    )
    (net (code "51") (name "Net-(U1-PROG)") (class "Default")
      (node (ref "R2") (pin "2") (pinfunction "2_2") (pintype "unspecified"))
      (node (ref "U1") (pin "2") (pinfunction "PROG_2") (pintype "unspecified"))
    )
    (net (code "52") (name "Net-(U3-CSB)") (class "Default")
      (node (ref "R9") (pin "1") (pinfunction "1_1") (pintype "unspecified"))
      (node (ref "U3") (pin "6") (pinfunction "CSB_6") (pintype "unspecified"))
    )
    (net (code "53") (name "Net-(U3-INT)") (class "Default")
      (node (ref "R15") (pin "1") (pinfunction "1_1") (pintype "input"))
      (node (ref "U3") (pin "7") (pinfunction "INT_7") (pintype "unspecified"))
    )
    (net (code "54") (name "Net-(U4-CPOUT)") (class "Default")
      (node (ref "C16") (pin "1") (pinfunction "1_1") (pintype "unspecified"))
      (node (ref "U4") (pin "20") (pinfunction "CPOUT_20") (pintype "unspecified"))
    )
    (net (code "55") (name "Net-(U4-INT)") (class "Default")
      (node (ref "R14") (pin "1") (pinfunction "1_1") (pintype "input"))
      (node (ref "U4") (pin "12") (pinfunction "INT_12") (pintype "unspecified"))
    )
    (net (code "56") (name "Net-(U6-VBUS)") (class "Default")
      (node (ref "R17") (pin "1") (pinfunction "1_1") (pintype "input"))
      (node (ref "U6") (pin "8") (pinfunction "VBUS_8") (pintype "unspecified"))
    )
    (net (code "57") (name "Net-(U6-VIN-)") (class "Default")
      (node (ref "R5") (pin "1") (pinfunction "1_1") (pintype "unspecified"))
      (node (ref "U6") (pin "9") (pinfunction "VIN-_9") (pintype "unspecified"))
    )
    (net (code "58") (name "Net-(U7-OUT)") (class "Default")
      (node (ref "R12") (pin "2") (pinfunction "2_2") (pintype "input"))
      (node (ref "U7") (pin "1") (pinfunction "OUT_1") (pintype "unspecified"))
    )
    (net (code "59") (name "PUFF") (class "Default")
      (node (ref "U10") (pin "OUT") (pinfunction "3_OUT") (pintype "unspecified"))
      (node (ref "U2") (pin "23") (pinfunction "IO21_23") (pintype "unspecified"))
      (node (ref "U9") (pin "2") (pinfunction "2_2") (pintype "input"))
    )
    (net (code "60") (name "RST") (class "Default")
      (node (ref "U11") (pin "5") (pinfunction "5_5") (pintype "input"))
      (node (ref "U2") (pin "9") (pinfunction "IO16_9") (pintype "unspecified"))
    )
    (net (code "61") (name "SDGATE") (class "Default")
      (node (ref "Q5") (pin "1") (pinfunction "G_1") (pintype "unspecified"))
      (node (ref "R23") (pin "1") (pinfunction "1_1") (pintype "unspecified"))
      (node (ref "R24") (pin "1") (pinfunction "1_1") (pintype "input"))
      (node (ref "U2") (pin "31") (pinfunction "IO38_31") (pintype "unspecified"))
      (node (ref "U9") (pin "14") (pinfunction "14_14") (pintype "input"))
    )
    (net (code "62") (name "SDVCC") (class "Default")
      (node (ref "C22") (pin "1") (pinfunction "1_1") (pintype "input"))
      (node (ref "Q5") (pin "3") (pinfunction "D_3") (pintype "unspecified"))
      (node (ref "R24") (pin "2") (pinfunction "2_2") (pintype "input"))
      (node (ref "TF1") (pin "4") (pinfunction "VDD_4") (pintype "unspecified"))
    )
    (net (code "63") (name "STANDBY") (class "Default")
      (node (ref "U1") (pin "6") (pinfunction "STDBY_6") (pintype "unspecified"))
    )
    (net (code "64") (name "U0RXD") (class "Default")
      (node (ref "U2") (pin "36") (pinfunction "RXD0_36") (pintype "unspecified"))
      (node (ref "U9") (pin "12") (pinfunction "12_12") (pintype "input"))
    )
    (net (code "65") (name "U0TXD") (class "Default")
      (node (ref "U2") (pin "37") (pinfunction "TXD0_37") (pintype "unspecified"))
      (node (ref "U9") (pin "13") (pinfunction "13_13") (pintype "input"))
    )
    (net (code "66") (name "USBD+") (class "Default")
      (node (ref "U12") (pin "3") (pinfunction "3_3") (pintype "input"))
      (node (ref "U2") (pin "14") (pinfunction "IO20_14") (pintype "unspecified"))
      (node (ref "U9") (pin "26") (pinfunction "26_26") (pintype "input"))
    )
    (net (code "67") (name "USBD-") (class "Default")
      (node (ref "U12") (pin "2") (pinfunction "2_2") (pintype "input"))
      (node (ref "U2") (pin "13") (pinfunction "IO19_13") (pintype "unspecified"))
      (node (ref "U9") (pin "25") (pinfunction "25_25") (pintype "input"))
    )
    (net (code "68") (name "USB_5V") (class "Default")
      (node (ref "C4") (pin "1") (pinfunction "1_1") (pintype "unspecified"))
      (node (ref "U1") (pin "4") (pinfunction "VCC_4") (pintype "unspecified"))
      (node (ref "U1") (pin "8") (pinfunction "CE_8") (pintype "unspecified"))
      (node (ref "U12") (pin "4") (pinfunction "4_4") (pintype "input"))
    )
    (net (code "69") (name "VIN") (class "Default")
      (node (ref "J2") (pin "2") (pinfunction "2_2") (pintype "unspecified"))
    )
    (net (code "70") (name "unconnected-(C17-Pad1)") (class "Default")
      (node (ref "C17") (pin "1") (pinfunction "1_1") (pintype "unspecified"))
    )
    (net (code "71") (name "unconnected-(TF1-DAT1-Pad8)") (class "Default")
      (node (ref "TF1") (pin "8") (pinfunction "DAT1_8") (pintype "unspecified+no_connect"))
    )
    (net (code "72") (name "unconnected-(TF1-DAT2-Pad1)") (class "Default")
      (node (ref "TF1") (pin "1") (pinfunction "DAT2_1") (pintype "unspecified+no_connect"))
    )
    (net (code "73") (name "unconnected-(U4-AUX_CL-Pad7)") (class "Default")
      (node (ref "U4") (pin "7") (pinfunction "AUX_CL_7") (pintype "unspecified"))
    )
    (net (code "74") (name "unconnected-(U4-AUX_DA-Pad6)") (class "Default")
      (node (ref "U4") (pin "6") (pinfunction "AUX_DA_6") (pintype "unspecified"))
    )
    (net (code "75") (name "unconnected-(U4-NC-Pad2)") (class "Default")
      (node (ref "U4") (pin "2") (pinfunction "NC_2") (pintype "unspecified"))
    )
    (net (code "76") (name "unconnected-(U4-NC-Pad3)") (class "Default")
      (node (ref "U4") (pin "3") (pinfunction "NC_3") (pintype "unspecified"))
    )
    (net (code "77") (name "unconnected-(U4-NC-Pad4)") (class "Default")
      (node (ref "U4") (pin "4") (pinfunction "NC_4") (pintype "unspecified"))
    )
    (net (code "78") (name "unconnected-(U4-NC-Pad5)") (class "Default")
      (node (ref "U4") (pin "5") (pinfunction "NC_5") (pintype "unspecified"))
    )
    (net (code "79") (name "unconnected-(U4-NC-Pad14)") (class "Default")
      (node (ref "U4") (pin "14") (pinfunction "NC_14") (pintype "unspecified"))
    )
    (net (code "80") (name "unconnected-(U4-NC-Pad15)") (class "Default")
      (node (ref "U4") (pin "15") (pinfunction "NC_15") (pintype "unspecified"))
    )
    (net (code "81") (name "unconnected-(U4-NC-Pad16)") (class "Default")
      (node (ref "U4") (pin "16") (pinfunction "NC_16") (pintype "unspecified"))
    )
    (net (code "82") (name "unconnected-(U4-NC-Pad17)") (class "Default")
      (node (ref "U4") (pin "17") (pinfunction "NC_17") (pintype "unspecified"))
    )
    (net (code "83") (name "unconnected-(U4-REGOUT-Pad10)") (class "Default")
      (node (ref "U4") (pin "10") (pinfunction "REGOUT_10") (pintype "unspecified"))
    )
    (net (code "84") (name "unconnected-(U4-RESV-Pad19)") (class "Default")
      (node (ref "U4") (pin "19") (pinfunction "RESV_19") (pintype "unspecified"))
    )
    (net (code "85") (name "unconnected-(U4-RESV-Pad21)") (class "Default")
      (node (ref "U4") (pin "21") (pinfunction "RESV_21") (pintype "unspecified"))
    )
    (net (code "86") (name "unconnected-(U4-RESV-Pad22)") (class "Default")
      (node (ref "U4") (pin "22") (pinfunction "RESV_22") (pintype "unspecified"))
    )
    (net (code "87") (name "unconnected-(U5-NC-Pad4)") (class "Default")
      (node (ref "U5") (pin "4") (pinfunction "NC_4") (pintype "unspecified+no_connect"))
    )
    (net (code "88") (name "unconnected-(U6-Alert-Pad3)") (class "Default")
      (node (ref "U6") (pin "3") (pinfunction "Alert_3") (pintype "unspecified+no_connect"))
    )
    (net (code "89") (name "unconnected-(U9-Pad20)") (class "Default")
      (node (ref "U9") (pin "20") (pinfunction "20_20") (pintype "input"))
    )
    (net (code "90") (name "unconnected-(U9-Pad31)") (class "Default")
      (node (ref "U9") (pin "31") (pinfunction "31_31") (pintype "input"))
    )
    (net (code "91") (name "unconnected-(U9-Pad32)") (class "Default")
      (node (ref "U9") (pin "32") (pinfunction "32_32") (pintype "input"))
    )
  )
)
